# NB_Bagde.net
KiCad netlist of a schematic drawn in Altium Designer
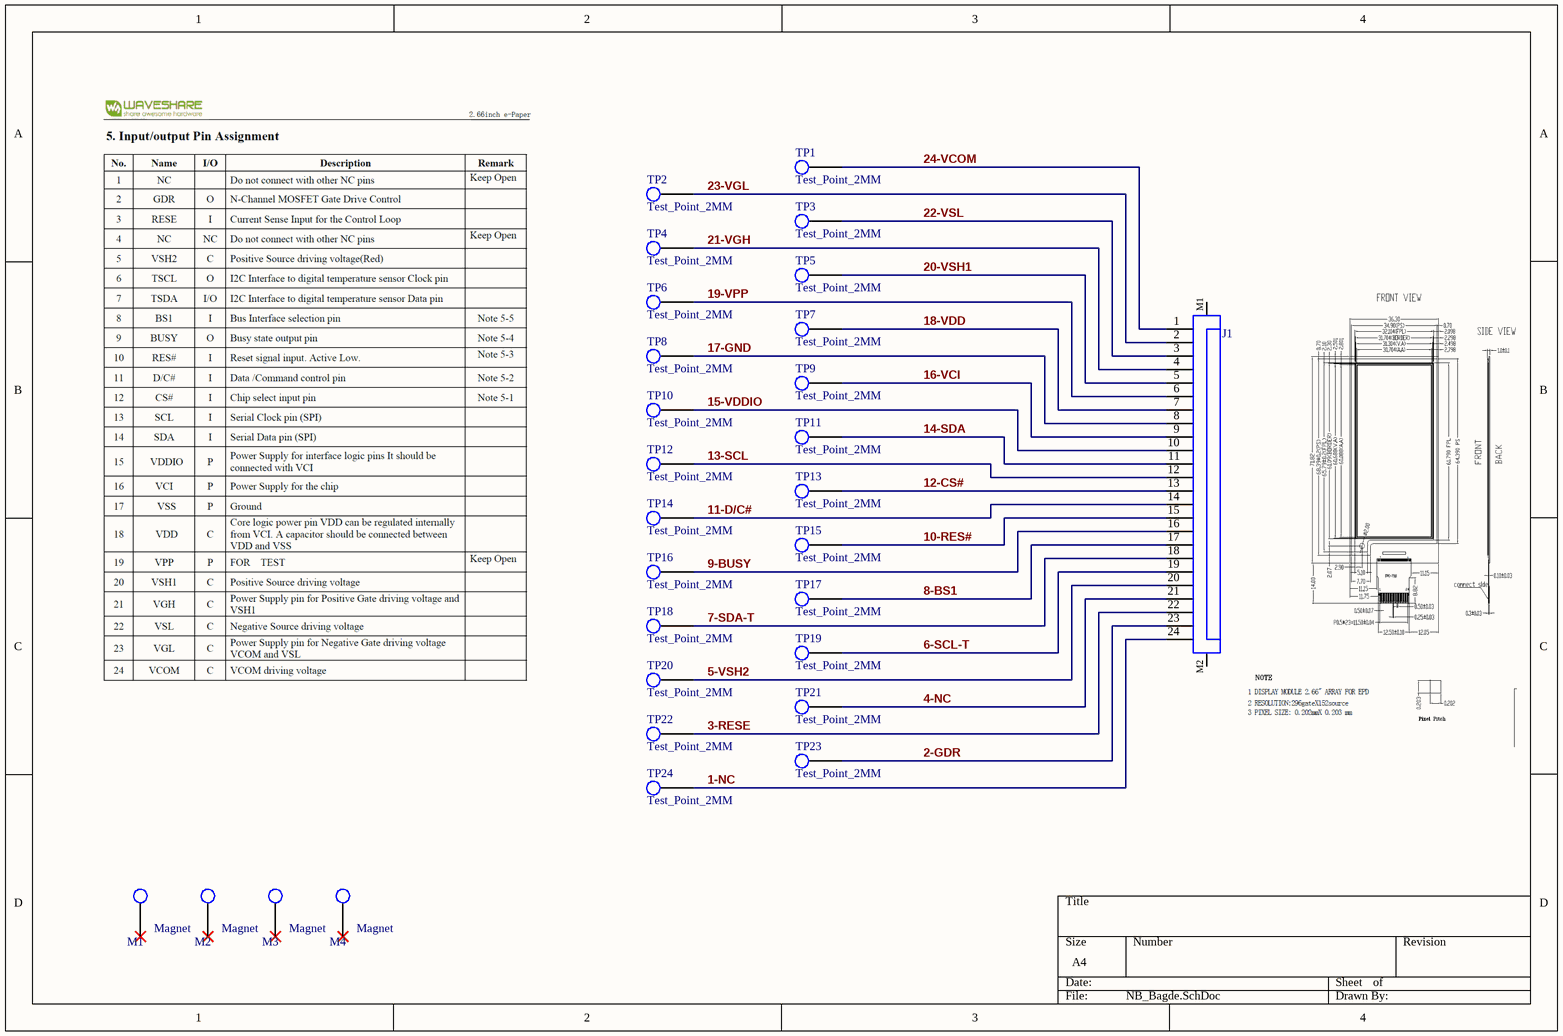
[diagram p0: NB_Bagde.SchDoc]

(export (version "E")
  (design (tool "Eeschema 10.0.6"))
  (components
    (comp (ref "J1")
      (value "687124182122")
      (footprint "687124182122")
      (description "WR-FPC SMT ZIF Horizontal Dual Contact, pitch 0.5mm, Horizontal, 24pins")
      (fields (field (name "MANUFACTURER") "Wurth Elektronik"))
      (libsource (lib "Schlib") (part "687124182122"))
    )
    (comp (ref "M1")
      (value "Magnet")
      (footprint "Magnet")
      (description "Magnet 3x2mm")
      (libsource (lib "Schlib") (part "Magnet"))
    )
    (comp (ref "M2")
      (value "Magnet")
      (footprint "Magnet")
      (description "Magnet 3x2mm")
      (libsource (lib "Schlib") (part "Magnet"))
    )
    (comp (ref "M3")
      (value "Magnet")
      (footprint "Magnet")
      (description "Magnet 3x2mm")
      (libsource (lib "Schlib") (part "Magnet"))
    )
    (comp (ref "M4")
      (value "Magnet")
      (footprint "Magnet")
      (description "Magnet 3x2mm")
      (libsource (lib "Schlib") (part "Magnet"))
    )
    (comp (ref "TP1")
      (value "Test_Point_2MM")
      (footprint "Test_Point_2mm")
      (description "Test Point")
      (libsource (lib "Schlib") (part "Test_Point_2MM"))
    )
    (comp (ref "TP2")
      (value "Test_Point_2MM")
      (footprint "Test_Point_2mm")
      (description "Test Point")
      (libsource (lib "Schlib") (part "Test_Point_2MM"))
    )
    (comp (ref "TP3")
      (value "Test_Point_2MM")
      (footprint "Test_Point_2mm")
      (description "Test Point")
      (libsource (lib "Schlib") (part "Test_Point_2MM"))
    )
    (comp (ref "TP4")
      (value "Test_Point_2MM")
      (footprint "Test_Point_2mm")
      (description "Test Point")
      (libsource (lib "Schlib") (part "Test_Point_2MM"))
    )
    (comp (ref "TP5")
      (value "Test_Point_2MM")
      (footprint "Test_Point_2mm")
      (description "Test Point")
      (libsource (lib "Schlib") (part "Test_Point_2MM"))
    )
    (comp (ref "TP6")
      (value "Test_Point_2MM")
      (footprint "Test_Point_2mm")
      (description "Test Point")
      (libsource (lib "Schlib") (part "Test_Point_2MM"))
    )
    (comp (ref "TP7")
      (value "Test_Point_2MM")
      (footprint "Test_Point_2mm")
      (description "Test Point")
      (libsource (lib "Schlib") (part "Test_Point_2MM"))
    )
    (comp (ref "TP8")
      (value "Test_Point_2MM")
      (footprint "Test_Point_2mm")
      (description "Test Point")
      (libsource (lib "Schlib") (part "Test_Point_2MM"))
    )
    (comp (ref "TP9")
      (value "Test_Point_2MM")
      (footprint "Test_Point_2mm")
      (description "Test Point")
      (libsource (lib "Schlib") (part "Test_Point_2MM"))
    )
    (comp (ref "TP10")
      (value "Test_Point_2MM")
      (footprint "Test_Point_2mm")
      (description "Test Point")
      (libsource (lib "Schlib") (part "Test_Point_2MM"))
    )
    (comp (ref "TP11")
      (value "Test_Point_2MM")
      (footprint "Test_Point_2mm")
      (description "Test Point")
      (libsource (lib "Schlib") (part "Test_Point_2MM"))
    )
    (comp (ref "TP12")
      (value "Test_Point_2MM")
      (footprint "Test_Point_2mm")
      (description "Test Point")
      (libsource (lib "Schlib") (part "Test_Point_2MM"))
    )
    (comp (ref "TP13")
      (value "Test_Point_2MM")
      (footprint "Test_Point_2mm")
      (description "Test Point")
      (libsource (lib "Schlib") (part "Test_Point_2MM"))
    )
    (comp (ref "TP14")
      (value "Test_Point_2MM")
      (footprint "Test_Point_2mm")
      (description "Test Point")
      (libsource (lib "Schlib") (part "Test_Point_2MM"))
    )
    (comp (ref "TP15")
      (value "Test_Point_2MM")
      (footprint "Test_Point_2mm")
      (description "Test Point")
      (libsource (lib "Schlib") (part "Test_Point_2MM"))
    )
    (comp (ref "TP16")
      (value "Test_Point_2MM")
      (footprint "Test_Point_2mm")
      (description "Test Point")
      (libsource (lib "Schlib") (part "Test_Point_2MM"))
    )
    (comp (ref "TP17")
      (value "Test_Point_2MM")
      (footprint "Test_Point_2mm")
      (description "Test Point")
      (libsource (lib "Schlib") (part "Test_Point_2MM"))
    )
    (comp (ref "TP18")
      (value "Test_Point_2MM")
      (footprint "Test_Point_2mm")
      (description "Test Point")
      (libsource (lib "Schlib") (part "Test_Point_2MM"))
    )
    (comp (ref "TP19")
      (value "Test_Point_2MM")
      (footprint "Test_Point_2mm")
      (description "Test Point")
      (libsource (lib "Schlib") (part "Test_Point_2MM"))
    )
    (comp (ref "TP20")
      (value "Test_Point_2MM")
      (footprint "Test_Point_2mm")
      (description "Test Point")
      (libsource (lib "Schlib") (part "Test_Point_2MM"))
    )
    (comp (ref "TP21")
      (value "Test_Point_2MM")
      (footprint "Test_Point_2mm")
      (description "Test Point")
      (libsource (lib "Schlib") (part "Test_Point_2MM"))
    )
    (comp (ref "TP22")
      (value "Test_Point_2MM")
      (footprint "Test_Point_2mm")
      (description "Test Point")
      (libsource (lib "Schlib") (part "Test_Point_2MM"))
    )
    (comp (ref "TP23")
      (value "Test_Point_2MM")
      (footprint "Test_Point_2mm")
      (description "Test Point")
      (libsource (lib "Schlib") (part "Test_Point_2MM"))
    )
    (comp (ref "TP24")
      (value "Test_Point_2MM")
      (footprint "Test_Point_2mm")
      (description "Test Point")
      (libsource (lib "Schlib") (part "Test_Point_2MM"))
    )
  )
  (nets
    (net (code "1") (name "/1-NC") (class "Default")
      (node (ref "J1") (pin "24") (pinfunction "24_24") (pintype "passive"))
      (node (ref "TP24") (pin "1") (pintype "passive"))
    )
    (net (code "2") (name "/2-GDR") (class "Default")
      (node (ref "J1") (pin "23") (pinfunction "23_23") (pintype "passive"))
      (node (ref "TP23") (pin "1") (pintype "passive"))
    )
    (net (code "3") (name "/3-RESE") (class "Default")
      (node (ref "J1") (pin "22") (pinfunction "22_22") (pintype "passive"))
      (node (ref "TP22") (pin "1") (pintype "passive"))
    )
    (net (code "4") (name "/4-NC") (class "Default")
      (node (ref "J1") (pin "21") (pinfunction "21_21") (pintype "passive"))
      (node (ref "TP21") (pin "1") (pintype "passive"))
    )
    (net (code "5") (name "/5-VSH2") (class "Default")
      (node (ref "J1") (pin "20") (pinfunction "20_20") (pintype "passive"))
      (node (ref "TP20") (pin "1") (pintype "passive"))
    )
    (net (code "6") (name "/6-SCL-T") (class "Default")
      (node (ref "J1") (pin "19") (pinfunction "19_19") (pintype "passive"))
      (node (ref "TP19") (pin "1") (pintype "passive"))
    )
    (net (code "7") (name "/7-SDA-T") (class "Default")
      (node (ref "J1") (pin "18") (pinfunction "18_18") (pintype "passive"))
      (node (ref "TP18") (pin "1") (pintype "passive"))
    )
    (net (code "8") (name "/8-BS1") (class "Default")
      (node (ref "J1") (pin "17") (pinfunction "17_17") (pintype "passive"))
      (node (ref "TP17") (pin "1") (pintype "passive"))
    )
    (net (code "9") (name "/9-BUSY") (class "Default")
      (node (ref "J1") (pin "16") (pinfunction "16_16") (pintype "passive"))
      (node (ref "TP16") (pin "1") (pintype "passive"))
    )
    (net (code "10") (name "/10-RES#") (class "Default")
      (node (ref "J1") (pin "15") (pinfunction "15_15") (pintype "passive"))
      (node (ref "TP15") (pin "1") (pintype "passive"))
    )
    (net (code "11") (name "/11-D{slash}C#") (class "Default")
      (node (ref "J1") (pin "14") (pinfunction "14_14") (pintype "passive"))
      (node (ref "TP14") (pin "1") (pintype "passive"))
    )
    (net (code "12") (name "/12-CS#") (class "Default")
      (node (ref "J1") (pin "13") (pinfunction "13_13") (pintype "passive"))
      (node (ref "TP13") (pin "1") (pintype "passive"))
    )
    (net (code "13") (name "/13-SCL") (class "Default")
      (node (ref "J1") (pin "12") (pinfunction "12_12") (pintype "passive"))
      (node (ref "TP12") (pin "1") (pintype "passive"))
    )
    (net (code "14") (name "/14-SDA") (class "Default")
      (node (ref "J1") (pin "11") (pinfunction "11_11") (pintype "passive"))
      (node (ref "TP11") (pin "1") (pintype "passive"))
    )
    (net (code "15") (name "/15-VDDIO") (class "Default")
      (node (ref "J1") (pin "10") (pinfunction "10_10") (pintype "passive"))
      (node (ref "TP10") (pin "1") (pintype "passive"))
    )
    (net (code "16") (name "/16-VCI") (class "Default")
      (node (ref "J1") (pin "9") (pinfunction "9_9") (pintype "passive"))
      (node (ref "TP9") (pin "1") (pintype "passive"))
    )
    (net (code "17") (name "/17-GND") (class "Default")
      (node (ref "J1") (pin "8") (pinfunction "8_8") (pintype "passive"))
      (node (ref "TP8") (pin "1") (pintype "passive"))
    )
    (net (code "18") (name "/18-VDD") (class "Default")
      (node (ref "J1") (pin "7") (pinfunction "7_7") (pintype "passive"))
      (node (ref "TP7") (pin "1") (pintype "passive"))
    )
    (net (code "19") (name "/19-VPP") (class "Default")
      (node (ref "J1") (pin "6") (pinfunction "6_6") (pintype "passive"))
      (node (ref "TP6") (pin "1") (pintype "passive"))
    )
    (net (code "20") (name "/20-VSH1") (class "Default")
      (node (ref "J1") (pin "5") (pinfunction "5_5") (pintype "passive"))
      (node (ref "TP5") (pin "1") (pintype "passive"))
    )
    (net (code "21") (name "/21-VGH") (class "Default")
      (node (ref "J1") (pin "4") (pinfunction "4_4") (pintype "passive"))
      (node (ref "TP4") (pin "1") (pintype "passive"))
    )
    (net (code "22") (name "/22-VSL") (class "Default")
      (node (ref "J1") (pin "3") (pinfunction "3_3") (pintype "passive"))
      (node (ref "TP3") (pin "1") (pintype "passive"))
    )
    (net (code "23") (name "/23-VGL") (class "Default")
      (node (ref "J1") (pin "2") (pinfunction "2_2") (pintype "passive"))
      (node (ref "TP2") (pin "1") (pintype "passive"))
    )
    (net (code "24") (name "/24-VCOM") (class "Default")
      (node (ref "J1") (pin "1") (pinfunction "1_1") (pintype "passive"))
      (node (ref "TP1") (pin "1") (pintype "passive"))
    )
    (net (code "25") (name "unconnected-(J1-PadM1)") (class "Default")
      (node (ref "J1") (pin "M1") (pinfunction "M1_M1") (pintype "passive"))
    )
    (net (code "26") (name "unconnected-(J1-PadM2)") (class "Default")
      (node (ref "J1") (pin "M2") (pinfunction "M2_M2") (pintype "passive"))
    )
    (net (code "27") (name "unconnected-(M1-Pad1)") (class "Default")
      (node (ref "M1") (pin "1") (pintype "passive+no_connect"))
    )
    (net (code "28") (name "unconnected-(M2-Pad1)") (class "Default")
      (node (ref "M2") (pin "1") (pintype "passive+no_connect"))
    )
    (net (code "29") (name "unconnected-(M3-Pad1)") (class "Default")
      (node (ref "M3") (pin "1") (pintype "passive+no_connect"))
    )
    (net (code "30") (name "unconnected-(M4-Pad1)") (class "Default")
      (node (ref "M4") (pin "1") (pintype "passive+no_connect"))
    )
  )
)
